# V1_5.net
KiCad netlist of a schematic drawn in Altium Designer
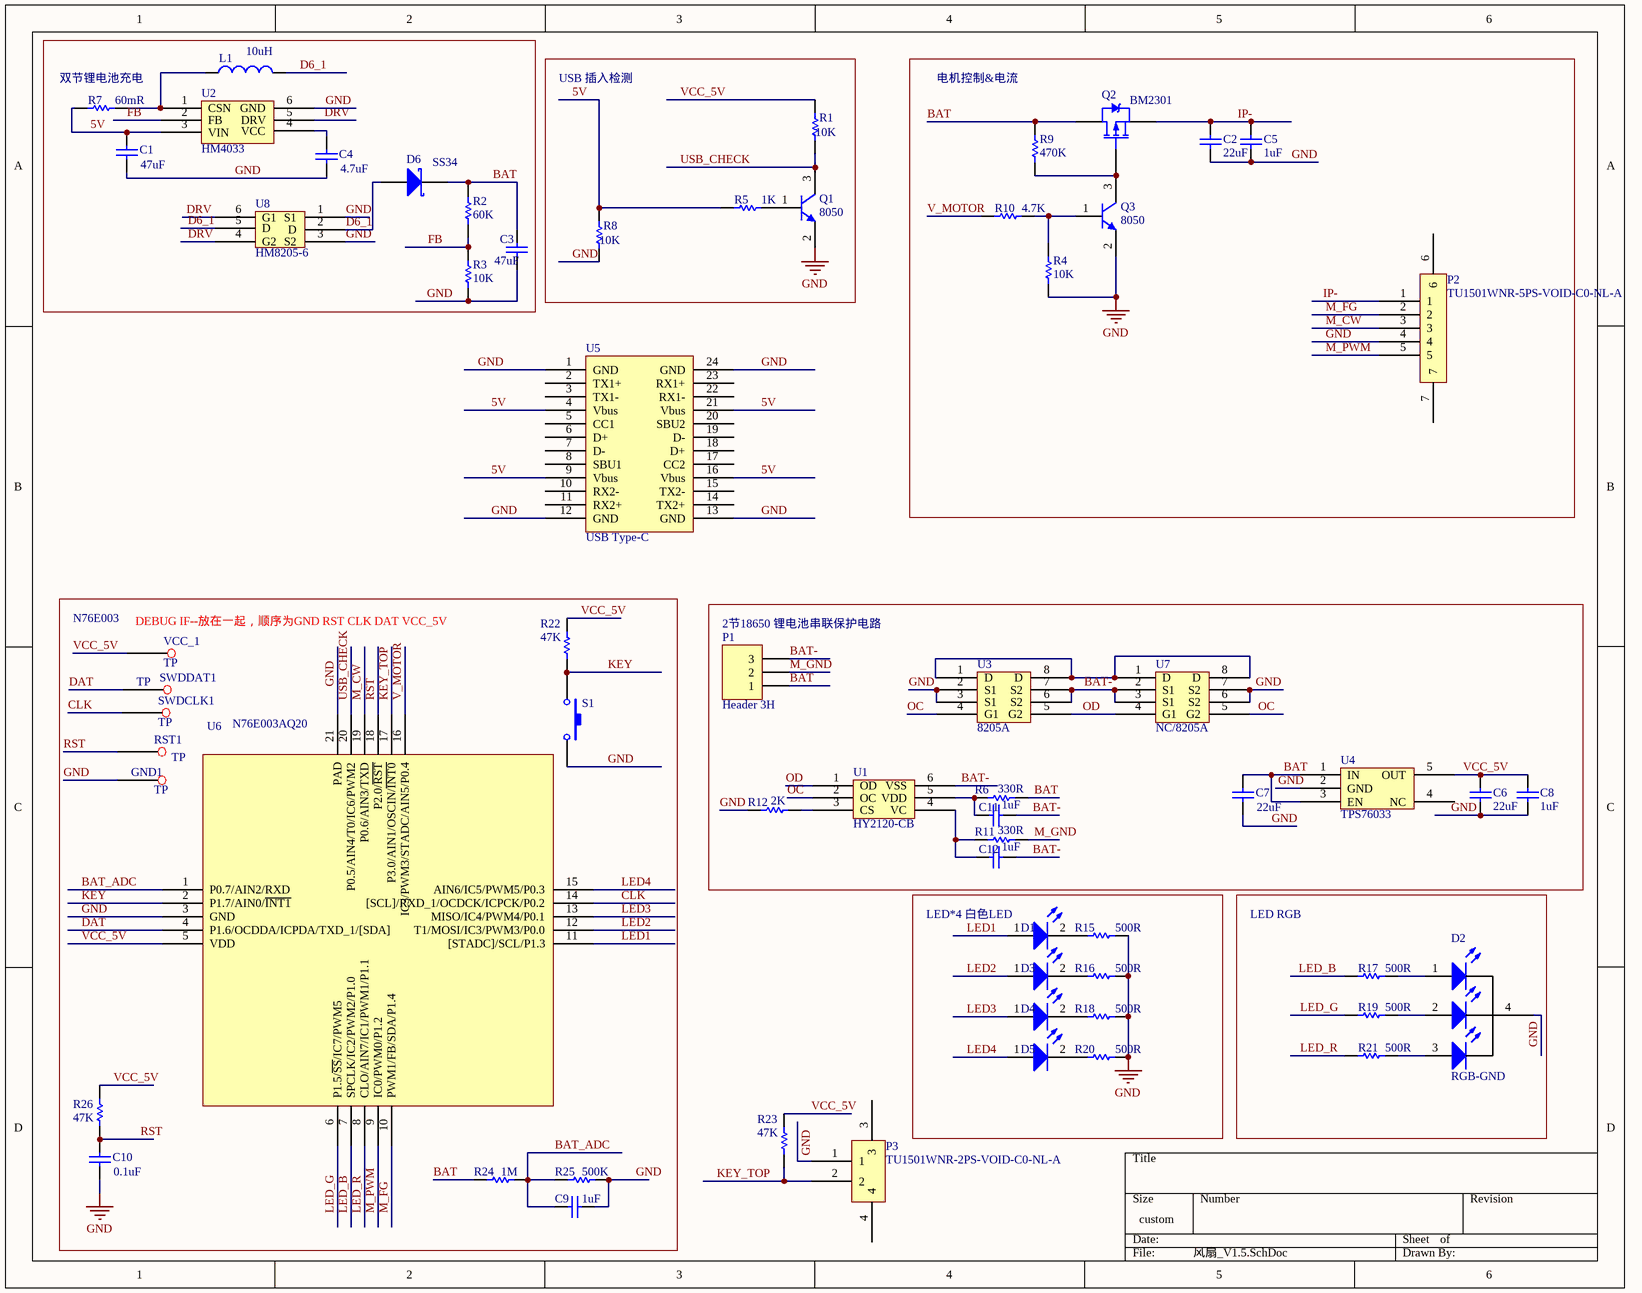
[diagram p0: 风扇_V1.5.SchDoc]

(export (version "E")
  (design (tool "Eeschema 10.0.6"))
  (components
    (comp (ref "C1")
      (value "47uF")
      (footprint "C-0603")
      (description "Capacitor")
      (fields (field (name "PUBLISHER") "Altium Limited"))
      (libsource (lib "Miscellaneous Devices") (part "Cap"))
    )
    (comp (ref "C2")
      (value "22uF")
      (footprint "C-0603")
      (description "Capacitor")
      (fields (field (name "PUBLISHER") "Altium Limited"))
      (libsource (lib "Miscellaneous Devices") (part "Cap"))
    )
    (comp (ref "C3")
      (value "47uF")
      (footprint "C-0603")
      (description "Capacitor")
      (fields (field (name "PUBLISHER") "Altium Limited"))
      (libsource (lib "Miscellaneous Devices") (part "Cap"))
    )
    (comp (ref "C4")
      (value "4.7uF")
      (footprint "C-0402")
      (description "Capacitor")
      (fields (field (name "PUBLISHER") "Altium Limited"))
      (libsource (lib "Miscellaneous Devices") (part "Cap"))
    )
    (comp (ref "C5")
      (value "1uF")
      (footprint "C-0402")
      (description "Capacitor")
      (fields (field (name "PUBLISHER") "Altium Limited"))
      (libsource (lib "Miscellaneous Devices") (part "Cap"))
    )
    (comp (ref "C6")
      (value "22uF")
      (footprint "C-0603")
      (description "Capacitor")
      (fields (field (name "PUBLISHER") "Altium Limited"))
      (libsource (lib "Miscellaneous Devices") (part "Cap"))
    )
    (comp (ref "C7")
      (value "22uF")
      (footprint "C-0603")
      (description "Capacitor")
      (fields (field (name "PUBLISHER") "Altium Limited"))
      (libsource (lib "Miscellaneous Devices") (part "Cap"))
    )
    (comp (ref "C8")
      (value "1uF")
      (footprint "C-0402")
      (description "Capacitor")
      (fields (field (name "PUBLISHER") "Altium Limited"))
      (libsource (lib "Miscellaneous Devices") (part "Cap"))
    )
    (comp (ref "C9")
      (value "1uF")
      (footprint "C-0402")
      (description "Capacitor")
      (fields (field (name "PUBLISHER") "Altium Limited"))
      (libsource (lib "Miscellaneous Devices") (part "Cap"))
    )
    (comp (ref "C10")
      (value "0.1uF")
      (footprint "C-0402")
      (description "Capacitor")
      (fields (field (name "PUBLISHER") "Altium Limited"))
      (libsource (lib "Miscellaneous Devices") (part "Cap"))
    )
    (comp (ref "C11")
      (value "1uF")
      (footprint "C-0402")
      (description "Capacitor")
      (fields (field (name "PUBLISHER") "Altium Limited"))
      (libsource (lib "Miscellaneous Devices") (part "Cap"))
    )
    (comp (ref "C12")
      (value "1uF")
      (footprint "C-0402")
      (description "Capacitor")
      (fields (field (name "PUBLISHER") "Altium Limited"))
      (libsource (lib "Miscellaneous Devices") (part "Cap"))
    )
    (comp (ref "D1")
      (value "LED0")
      (footprint "LED-0603")
      (description "Typical INFRARED GaAs LED")
      (fields (field (name "PUBLISHER") "Altium Limited"))
      (libsource (lib "Miscellaneous Devices") (part "LED0"))
    )
    (comp (ref "D2")
      (value "RGB-GND")
      (footprint "0603*2-LED")
      (libsource (lib "Others_IC_SCH_LIB") (part "RGB-GND"))
    )
    (comp (ref "D3")
      (value "LED0")
      (footprint "LED-0603")
      (description "Typical INFRARED GaAs LED")
      (fields (field (name "PUBLISHER") "Altium Limited"))
      (libsource (lib "Miscellaneous Devices") (part "LED0"))
    )
    (comp (ref "D4")
      (value "LED0")
      (footprint "LED-0603")
      (description "Typical INFRARED GaAs LED")
      (fields (field (name "PUBLISHER") "Altium Limited"))
      (libsource (lib "Miscellaneous Devices") (part "LED0"))
    )
    (comp (ref "D5")
      (value "LED0")
      (footprint "LED-0603")
      (description "Typical INFRARED GaAs LED")
      (fields (field (name "PUBLISHER") "Altium Limited"))
      (libsource (lib "Miscellaneous Devices") (part "LED0"))
    )
    (comp (ref "D6")
      (value "SS34")
      (footprint "HM4033 V1.0:DSMD")
      (description "Schottky Rectifier")
      (fields (field (name "PUBLISHER") "Altium Limited"))
      (libsource (lib "Miscellaneous Devices") (part "Diode 10TQ035"))
    )
    (comp (ref "GND1") (value "TP") (footprint "TP-1.5") (libsource (lib "Others_IC_SCH_LIB") (part "TP")))
    (comp (ref "L1")
      (value "10uH")
      (footprint "L-SMD")
      (description "Inductor")
      (fields (field (name "PUBLISHER") "Altium Limited"))
      (libsource (lib "Miscellaneous Devices") (part "Inductor"))
    )
    (comp (ref "P1")
      (value "Header 3H")
      (footprint "3P-SMT-3*3")
      (description "Header, 3-Pin, Right Angle")
      (fields (field (name "PUBLISHER") "Altium Limited"))
      (libsource (lib "Miscellaneous Connectors") (part "Header 3H"))
    )
    (comp (ref "P2")
      (value "TU1501WNR-5PS-VOID-C0-NL-A")
      (footprint "TU1501WNR-5PS-VOID-*-NL-A")
      (libsource (lib "Others_IC_SCH_LIB") (part "TU1501WNR-5PS-VOID-C0-NL-A"))
    )
    (comp (ref "P3")
      (value "TU1501WNR-2PS-VOID-C0-NL-A")
      (footprint "TU1501WNR-2PS-VOID-*-NL-A")
      (libsource (lib "Others_IC_SCH_LIB") (part "TU1501WNR-2PS-VOID-C0-NL-A"))
    )
    (comp (ref "Q1")
      (value "8050")
      (footprint "SOT-23")
      (description "NPN Bipolar Transistor")
      (fields (field (name "PUBLISHER") "Altium Limited"))
      (libsource (lib "Miscellaneous Devices") (part "NPN"))
    )
    (comp (ref "Q2")
      (value "BM2301")
      (footprint "SOT-23")
      (description "P-Channel Power MOSFET")
      (fields (field (name "PUBLISHER") "Altium Limited"))
      (libsource (lib "Miscellaneous Devices") (part "PMOS-2"))
    )
    (comp (ref "Q3")
      (value "8050")
      (footprint "SOT-23")
      (description "NPN Bipolar Transistor")
      (fields (field (name "PUBLISHER") "Altium Limited"))
      (libsource (lib "Miscellaneous Devices") (part "NPN"))
    )
    (comp (ref "R1")
      (value "10K")
      (footprint "R-0402")
      (description "Resistor")
      (fields (field (name "PUBLISHER") "Altium Limited"))
      (libsource (lib "Miscellaneous Devices") (part "Res1"))
    )
    (comp (ref "R2")
      (value "60K")
      (footprint "R-0402")
      (description "Resistor")
      (fields (field (name "PUBLISHER") "Altium Limited"))
      (libsource (lib "Miscellaneous Devices") (part "Res1"))
    )
    (comp (ref "R3")
      (value "10K")
      (footprint "R-0402")
      (description "Resistor")
      (fields (field (name "PUBLISHER") "Altium Limited"))
      (libsource (lib "Miscellaneous Devices") (part "Res1"))
    )
    (comp (ref "R4")
      (value "10K")
      (footprint "R-0402")
      (description "Resistor")
      (fields (field (name "PUBLISHER") "Altium Limited"))
      (libsource (lib "Miscellaneous Devices") (part "Res1"))
    )
    (comp (ref "R5")
      (value "1K")
      (footprint "R-0402")
      (description "Resistor")
      (fields (field (name "PUBLISHER") "Altium Limited"))
      (libsource (lib "Miscellaneous Devices") (part "Res1"))
    )
    (comp (ref "R6")
      (value "330R")
      (footprint "R-0402")
      (description "Resistor")
      (fields (field (name "PUBLISHER") "Altium Limited"))
      (libsource (lib "Miscellaneous Devices") (part "Res1"))
    )
    (comp (ref "R7")
      (value "60mR")
      (footprint "R-0402")
      (description "Resistor")
      (fields (field (name "PUBLISHER") "Altium Limited"))
      (libsource (lib "Miscellaneous Devices") (part "Res1"))
    )
    (comp (ref "R8")
      (value "10K")
      (footprint "R-0402")
      (description "Resistor")
      (fields (field (name "PUBLISHER") "Altium Limited"))
      (libsource (lib "Miscellaneous Devices") (part "Res1"))
    )
    (comp (ref "R9")
      (value "470K")
      (footprint "R-0402")
      (description "Resistor")
      (fields (field (name "PUBLISHER") "Altium Limited"))
      (libsource (lib "Miscellaneous Devices") (part "Res1"))
    )
    (comp (ref "R10")
      (value "4.7K")
      (footprint "R-0402")
      (description "Resistor")
      (fields (field (name "PUBLISHER") "Altium Limited"))
      (libsource (lib "Miscellaneous Devices") (part "Res1"))
    )
    (comp (ref "R11")
      (value "330R")
      (footprint "R-0402")
      (description "Resistor")
      (fields (field (name "PUBLISHER") "Altium Limited"))
      (libsource (lib "Miscellaneous Devices") (part "Res1"))
    )
    (comp (ref "R12")
      (value "2K")
      (footprint "R-0402")
      (description "Resistor")
      (fields (field (name "PUBLISHER") "Altium Limited"))
      (libsource (lib "Miscellaneous Devices") (part "Res1"))
    )
    (comp (ref "R15")
      (value "500R")
      (footprint "R-0402")
      (description "Resistor")
      (fields (field (name "PUBLISHER") "Altium Limited"))
      (libsource (lib "Miscellaneous Devices") (part "Res1"))
    )
    (comp (ref "R16")
      (value "500R")
      (footprint "R-0402")
      (description "Resistor")
      (fields (field (name "PUBLISHER") "Altium Limited"))
      (libsource (lib "Miscellaneous Devices") (part "Res1"))
    )
    (comp (ref "R17")
      (value "500R")
      (footprint "R-0402")
      (description "Resistor")
      (fields (field (name "PUBLISHER") "Altium Limited"))
      (libsource (lib "Miscellaneous Devices") (part "Res1"))
    )
    (comp (ref "R18")
      (value "500R")
      (footprint "R-0402")
      (description "Resistor")
      (fields (field (name "PUBLISHER") "Altium Limited"))
      (libsource (lib "Miscellaneous Devices") (part "Res1"))
    )
    (comp (ref "R19")
      (value "500R")
      (footprint "R-0402")
      (description "Resistor")
      (fields (field (name "PUBLISHER") "Altium Limited"))
      (libsource (lib "Miscellaneous Devices") (part "Res1"))
    )
    (comp (ref "R20")
      (value "500R")
      (footprint "R-0402")
      (description "Resistor")
      (fields (field (name "PUBLISHER") "Altium Limited"))
      (libsource (lib "Miscellaneous Devices") (part "Res1"))
    )
    (comp (ref "R21")
      (value "500R")
      (footprint "R-0402")
      (description "Resistor")
      (fields (field (name "PUBLISHER") "Altium Limited"))
      (libsource (lib "Miscellaneous Devices") (part "Res1"))
    )
    (comp (ref "R22")
      (value "47K")
      (footprint "R-0402")
      (description "Resistor")
      (fields (field (name "PUBLISHER") "Altium Limited"))
      (libsource (lib "Miscellaneous Devices") (part "Res1"))
    )
    (comp (ref "R23")
      (value "47K")
      (footprint "R-0402")
      (description "Resistor")
      (fields (field (name "PUBLISHER") "Altium Limited"))
      (libsource (lib "Miscellaneous Devices") (part "Res1"))
    )
    (comp (ref "R24")
      (value "1M")
      (footprint "R-0402")
      (description "Resistor")
      (fields (field (name "PUBLISHER") "Altium Limited"))
      (libsource (lib "Miscellaneous Devices") (part "Res1"))
    )
    (comp (ref "R25")
      (value "500K")
      (footprint "R-0402")
      (description "Resistor")
      (fields (field (name "PUBLISHER") "Altium Limited"))
      (libsource (lib "Miscellaneous Devices") (part "Res1"))
    )
    (comp (ref "R26")
      (value "47K")
      (footprint "R-0402")
      (description "Resistor")
      (fields (field (name "PUBLISHER") "Altium Limited"))
      (libsource (lib "Miscellaneous Devices") (part "Res1"))
    )
    (comp (ref "RST1") (value "TP") (footprint "TP-1.5") (libsource (lib "Others_IC_SCH_LIB") (part "TP")))
    (comp (ref "S1")
      (value "SW-PB")
      (footprint "SWITCH-4P-SMT")
      (description "Switch")
      (fields (field (name "PUBLISHER") "Altium Limited"))
      (libsource (lib "Miscellaneous Devices") (part "SW-PB"))
    )
    (comp (ref "SWDCLK1") (value "TP") (footprint "TP-1.5") (libsource (lib "Others_IC_SCH_LIB") (part "TP")))
    (comp (ref "SWDDAT1") (value "TP") (footprint "TP-1.5") (libsource (lib "Others_IC_SCH_LIB") (part "TP")))
    (comp (ref "U1")
      (value "HY2120-CB")
      (footprint "SOT-23-6L")
      (libsource (lib "Others_IC_SCH_LIB") (part "HY2120"))
    )
    (comp (ref "U2")
      (value "HM4033")
      (footprint "SOT-23-6L")
      (libsource (lib "Others_IC_SCH_LIB") (part "HM4033"))
    )
    (comp (ref "U3")
      (value "8205A")
      (footprint "TSSOP8")
      (libsource (lib "Others_IC_SCH_LIB") (part "8205A"))
    )
    (comp (ref "U4")
      (value "TPS76033")
      (footprint "SOT-23-5")
      (libsource (lib "Others_IC_SCH_LIB") (part "TPS76033"))
    )
    (comp (ref "U5")
      (value "USB Type-C")
      (footprint "USB-type C")
      (libsource (lib "Others_IC_SCH_LIB") (part "USB Type-C"))
    )
    (comp (ref "U6")
      (value "N76E003AQ20")
      (footprint "QFN-20 0.4mm")
      (libsource (lib "Others_IC_SCH_LIB") (part "N76E003AQ20"))
    )
    (comp (ref "U7")
      (value "NC/8205A")
      (footprint "TSSOP8")
      (libsource (lib "Others_IC_SCH_LIB") (part "8205A"))
    )
    (comp (ref "U8")
      (value "HM8205-6")
      (footprint "SOT-23-6L")
      (libsource (lib "Others_IC_SCH_LIB") (part "HM8205-6"))
    )
    (comp (ref "VCC_1") (value "TP") (footprint "TP-1.5") (libsource (lib "Others_IC_SCH_LIB") (part "TP")))
  )
  (nets
    (net (code "1") (name "/5V") (class "Default")
      (node (ref "C1") (pin "1") (pinfunction "1_1") (pintype "passive"))
      (node (ref "R5") (pin "1") (pinfunction "1_1") (pintype "passive"))
      (node (ref "R7") (pin "2") (pinfunction "2_2") (pintype "passive"))
      (node (ref "R8") (pin "1") (pinfunction "1_1") (pintype "passive"))
      (node (ref "U2") (pin "3") (pinfunction "VIN_3") (pintype "passive"))
      (node (ref "U5") (pin "16") (pinfunction "Vbus_16") (pintype "passive"))
      (node (ref "U5") (pin "21") (pinfunction "Vbus_21") (pintype "passive"))
      (node (ref "U5") (pin "4") (pinfunction "Vbus_4") (pintype "passive"))
      (node (ref "U5") (pin "9") (pinfunction "Vbus_9") (pintype "passive"))
    )
    (net (code "2") (name "/BAT") (class "Default")
      (node (ref "C3") (pin "2") (pinfunction "2_2") (pintype "passive"))
      (node (ref "C7") (pin "2") (pinfunction "2_2") (pintype "passive"))
      (node (ref "D6") (pin "1") (pinfunction "K_1") (pintype "passive"))
      (node (ref "P1") (pin "1") (pinfunction "1_1") (pintype "passive"))
      (node (ref "Q2") (pin "2") (pinfunction "D_2") (pintype "passive"))
      (node (ref "R2") (pin "1") (pinfunction "1_1") (pintype "passive"))
      (node (ref "R24") (pin "1") (pinfunction "1_1") (pintype "passive"))
      (node (ref "R6") (pin "2") (pinfunction "2_2") (pintype "passive"))
      (node (ref "R9") (pin "2") (pinfunction "2_2") (pintype "passive"))
      (node (ref "U4") (pin "1") (pinfunction "IN_1") (pintype "passive"))
      (node (ref "U4") (pin "3") (pinfunction "EN_3") (pintype "passive"))
    )
    (net (code "3") (name "/BAT-") (class "Default")
      (node (ref "C11") (pin "1") (pinfunction "1_1") (pintype "passive"))
      (node (ref "C12") (pin "1") (pinfunction "1_1") (pintype "passive"))
      (node (ref "P1") (pin "3") (pinfunction "3_3") (pintype "passive"))
      (node (ref "U1") (pin "6") (pinfunction "VSS_6") (pintype "passive"))
      (node (ref "U3") (pin "6") (pinfunction "S2_6") (pintype "passive"))
      (node (ref "U3") (pin "7") (pinfunction "S2_7") (pintype "passive"))
      (node (ref "U7") (pin "2") (pinfunction "S1_2") (pintype "passive"))
      (node (ref "U7") (pin "3") (pinfunction "S1_3") (pintype "passive"))
    )
    (net (code "4") (name "/BAT_ADC") (class "Default")
      (node (ref "C9") (pin "2") (pinfunction "2_2") (pintype "passive"))
      (node (ref "R24") (pin "2") (pinfunction "2_2") (pintype "passive"))
      (node (ref "R25") (pin "1") (pinfunction "1_1") (pintype "passive"))
      (node (ref "U6") (pin "1") (pinfunction "P0.7/AIN2/RXD_1") (pintype "passive"))
    )
    (net (code "5") (name "/CLK") (class "Default")
      (node (ref "SWDCLK1") (pin "1") (pinfunction "1_1") (pintype "passive"))
      (node (ref "U6") (pin "14") (pinfunction "[SCL]/RXD_1/OCDCK/ICPCK/P0.2_14") (pintype "passive"))
    )
    (net (code "6") (name "/D6_1") (class "Default")
      (node (ref "D6") (pin "3") (pinfunction "A_3") (pintype "passive"))
      (node (ref "L1") (pin "2") (pinfunction "2_2") (pintype "passive"))
      (node (ref "U8") (pin "2") (pinfunction "D_2") (pintype "passive"))
      (node (ref "U8") (pin "5") (pinfunction "D_5") (pintype "passive"))
    )
    (net (code "7") (name "/DAT") (class "Default")
      (node (ref "SWDDAT1") (pin "1") (pinfunction "1_1") (pintype "passive"))
      (node (ref "U6") (pin "4") (pinfunction "P1.6/OCDDA/ICPDA/TXD_1/[SDA]_4") (pintype "passive"))
    )
    (net (code "8") (name "/DRV") (class "Default")
      (node (ref "U2") (pin "5") (pinfunction "DRV_5") (pintype "passive"))
      (node (ref "U8") (pin "4") (pinfunction "G2_4") (pintype "passive"))
      (node (ref "U8") (pin "6") (pinfunction "G1_6") (pintype "passive"))
    )
    (net (code "9") (name "/FB") (class "Default")
      (node (ref "R2") (pin "2") (pinfunction "2_2") (pintype "passive"))
      (node (ref "R3") (pin "1") (pinfunction "1_1") (pintype "passive"))
      (node (ref "U2") (pin "2") (pinfunction "FB_2") (pintype "passive"))
    )
    (net (code "10") (name "/IP-") (class "Default")
      (node (ref "C2") (pin "2") (pinfunction "2_2") (pintype "passive"))
      (node (ref "C5") (pin "2") (pinfunction "2_2") (pintype "passive"))
      (node (ref "P2") (pin "1") (pinfunction "1_1") (pintype "passive"))
      (node (ref "Q2") (pin "3") (pinfunction "S_3") (pintype "passive"))
    )
    (net (code "11") (name "/KEY") (class "Default")
      (node (ref "R22") (pin "1") (pinfunction "1_1") (pintype "passive"))
      (node (ref "S1") (pin "1") (pinfunction "1_1") (pintype "passive"))
      (node (ref "U6") (pin "2") (pinfunction "P1.7/AIN0/~{INT1}_2") (pintype "passive"))
    )
    (net (code "12") (name "/KEY_TOP") (class "Default")
      (node (ref "P3") (pin "2") (pinfunction "2_2") (pintype "passive"))
      (node (ref "R23") (pin "1") (pinfunction "1_1") (pintype "passive"))
      (node (ref "U6") (pin "17") (pinfunction "P3.0/AIN1/OSCIN/~{INT0}_17") (pintype "passive"))
    )
    (net (code "13") (name "/LED1") (class "Default")
      (node (ref "D1") (pin "1") (pinfunction "A_1") (pintype "passive"))
      (node (ref "U6") (pin "11") (pinfunction "[STADC]/SCL/P1.3_11") (pintype "passive"))
    )
    (net (code "14") (name "/LED2") (class "Default")
      (node (ref "D3") (pin "1") (pinfunction "A_1") (pintype "passive"))
      (node (ref "U6") (pin "12") (pinfunction "T1/MOSI/IC3/PWM3/P0.0_12") (pintype "passive"))
    )
    (net (code "15") (name "/LED3") (class "Default")
      (node (ref "D4") (pin "1") (pinfunction "A_1") (pintype "passive"))
      (node (ref "U6") (pin "13") (pinfunction "MISO/IC4/PWM4/P0.1_13") (pintype "passive"))
    )
    (net (code "16") (name "/LED4") (class "Default")
      (node (ref "D5") (pin "1") (pinfunction "A_1") (pintype "passive"))
      (node (ref "U6") (pin "15") (pinfunction "AIN6/IC5/PWM5/P0.3_15") (pintype "passive"))
    )
    (net (code "17") (name "/LED_B") (class "Default")
      (node (ref "R17") (pin "1") (pinfunction "1_1") (pintype "passive"))
      (node (ref "U6") (pin "7") (pinfunction "SPCLK/IC2/PWM2/P1.0_7") (pintype "passive"))
    )
    (net (code "18") (name "/LED_G") (class "Default")
      (node (ref "R19") (pin "1") (pinfunction "1_1") (pintype "passive"))
      (node (ref "U6") (pin "6") (pinfunction "P1.5/~{SS}/IC7/PWM5_6") (pintype "passive"))
    )
    (net (code "19") (name "/LED_R") (class "Default")
      (node (ref "R21") (pin "1") (pinfunction "1_1") (pintype "passive"))
      (node (ref "U6") (pin "8") (pinfunction "CLO/AIN7/IC1/PWM1/P1.1_8") (pintype "passive"))
    )
    (net (code "20") (name "/M_CW") (class "Default")
      (node (ref "P2") (pin "3") (pinfunction "3_3") (pintype "passive"))
      (node (ref "U6") (pin "19") (pinfunction "P0.6/AIN3/TXD_19") (pintype "passive"))
    )
    (net (code "21") (name "/M_FG") (class "Default")
      (node (ref "P2") (pin "2") (pinfunction "2_2") (pintype "passive"))
      (node (ref "U6") (pin "10") (pinfunction "PWM1/FB/SDA/P1.4_10") (pintype "passive"))
    )
    (net (code "22") (name "/M_GND") (class "Default")
      (node (ref "P1") (pin "2") (pinfunction "2_2") (pintype "passive"))
      (node (ref "R11") (pin "2") (pinfunction "2_2") (pintype "passive"))
    )
    (net (code "23") (name "/M_PWM") (class "Default")
      (node (ref "P2") (pin "5") (pinfunction "5_5") (pintype "passive"))
      (node (ref "U6") (pin "9") (pinfunction "IC0/PWM0/P1.2_9") (pintype "passive"))
    )
    (net (code "24") (name "/OC") (class "Default")
      (node (ref "U1") (pin "2") (pinfunction "OC_2") (pintype "passive"))
      (node (ref "U3") (pin "4") (pinfunction "G1_4") (pintype "passive"))
      (node (ref "U7") (pin "5") (pinfunction "G2_5") (pintype "passive"))
    )
    (net (code "25") (name "/OD") (class "Default")
      (node (ref "U1") (pin "1") (pinfunction "OD_1") (pintype "passive"))
      (node (ref "U3") (pin "5") (pinfunction "G2_5") (pintype "passive"))
      (node (ref "U7") (pin "4") (pinfunction "G1_4") (pintype "passive"))
    )
    (net (code "26") (name "/RST") (class "Default")
      (node (ref "C10") (pin "2") (pinfunction "2_2") (pintype "passive"))
      (node (ref "R26") (pin "1") (pinfunction "1_1") (pintype "passive"))
      (node (ref "RST1") (pin "1") (pinfunction "1_1") (pintype "passive"))
      (node (ref "U6") (pin "18") (pinfunction "P2.0/~{RST}_18") (pintype "passive"))
    )
    (net (code "27") (name "/USB_CHECK") (class "Default")
      (node (ref "Q1") (pin "3") (pinfunction "C_3") (pintype "passive"))
      (node (ref "R1") (pin "1") (pinfunction "1_1") (pintype "passive"))
      (node (ref "U6") (pin "20") (pinfunction "P0.5/AIN4/T0/IC6/PWM2_20") (pintype "passive"))
    )
    (net (code "28") (name "/VCC_5V") (class "Default")
      (node (ref "C6") (pin "2") (pinfunction "2_2") (pintype "passive"))
      (node (ref "C8") (pin "2") (pinfunction "2_2") (pintype "passive"))
      (node (ref "R1") (pin "2") (pinfunction "2_2") (pintype "passive"))
      (node (ref "R22") (pin "2") (pinfunction "2_2") (pintype "passive"))
      (node (ref "R23") (pin "2") (pinfunction "2_2") (pintype "passive"))
      (node (ref "R26") (pin "2") (pinfunction "2_2") (pintype "passive"))
      (node (ref "U4") (pin "5") (pinfunction "OUT_5") (pintype "passive"))
      (node (ref "U6") (pin "5") (pinfunction "VDD_5") (pintype "passive"))
      (node (ref "VCC_1") (pin "1") (pinfunction "1_1") (pintype "passive"))
    )
    (net (code "29") (name "/V_MOTOR") (class "Default")
      (node (ref "R10") (pin "1") (pinfunction "1_1") (pintype "passive"))
      (node (ref "U6") (pin "16") (pinfunction "IC3/PWM3/STADC/AIN5/P0.4_16") (pintype "passive"))
    )
    (net (code "30") (name "GND") (class "Default")
      (node (ref "C1") (pin "2") (pinfunction "2_2") (pintype "passive"))
      (node (ref "C10") (pin "1") (pinfunction "1_1") (pintype "passive"))
      (node (ref "C2") (pin "1") (pinfunction "1_1") (pintype "passive"))
      (node (ref "C3") (pin "1") (pinfunction "1_1") (pintype "passive"))
      (node (ref "C4") (pin "2") (pinfunction "2_2") (pintype "passive"))
      (node (ref "C5") (pin "1") (pinfunction "1_1") (pintype "passive"))
      (node (ref "C6") (pin "1") (pinfunction "1_1") (pintype "passive"))
      (node (ref "C7") (pin "1") (pinfunction "1_1") (pintype "passive"))
      (node (ref "C8") (pin "1") (pinfunction "1_1") (pintype "passive"))
      (node (ref "C9") (pin "1") (pinfunction "1_1") (pintype "passive"))
      (node (ref "D2") (pin "4") (pinfunction "4_4") (pintype "passive"))
      (node (ref "GND1") (pin "1") (pinfunction "1_1") (pintype "passive"))
      (node (ref "P2") (pin "4") (pinfunction "4_4") (pintype "passive"))
      (node (ref "P3") (pin "1") (pinfunction "1_1") (pintype "passive"))
      (node (ref "Q1") (pin "2") (pinfunction "E_2") (pintype "passive"))
      (node (ref "Q3") (pin "2") (pinfunction "E_2") (pintype "passive"))
      (node (ref "R12") (pin "1") (pinfunction "1_1") (pintype "passive"))
      (node (ref "R15") (pin "2") (pinfunction "2_2") (pintype "passive"))
      (node (ref "R16") (pin "2") (pinfunction "2_2") (pintype "passive"))
      (node (ref "R18") (pin "2") (pinfunction "2_2") (pintype "passive"))
      (node (ref "R20") (pin "2") (pinfunction "2_2") (pintype "passive"))
      (node (ref "R25") (pin "2") (pinfunction "2_2") (pintype "passive"))
      (node (ref "R3") (pin "2") (pinfunction "2_2") (pintype "passive"))
      (node (ref "R4") (pin "1") (pinfunction "1_1") (pintype "passive"))
      (node (ref "R8") (pin "2") (pinfunction "2_2") (pintype "passive"))
      (node (ref "S1") (pin "2") (pinfunction "2_2") (pintype "passive"))
      (node (ref "U2") (pin "6") (pinfunction "GND_6") (pintype "passive"))
      (node (ref "U3") (pin "2") (pinfunction "S1_2") (pintype "passive"))
      (node (ref "U3") (pin "3") (pinfunction "S1_3") (pintype "passive"))
      (node (ref "U4") (pin "2") (pinfunction "GND_2") (pintype "passive"))
      (node (ref "U5") (pin "1") (pinfunction "GND_1") (pintype "passive"))
      (node (ref "U5") (pin "12") (pinfunction "GND_12") (pintype "passive"))
      (node (ref "U5") (pin "13") (pinfunction "GND_13") (pintype "passive"))
      (node (ref "U5") (pin "24") (pinfunction "GND_24") (pintype "passive"))
      (node (ref "U6") (pin "21") (pinfunction "PAD_21") (pintype "passive"))
      (node (ref "U6") (pin "3") (pinfunction "GND_3") (pintype "passive"))
      (node (ref "U7") (pin "6") (pinfunction "S2_6") (pintype "passive"))
      (node (ref "U7") (pin "7") (pinfunction "S2_7") (pintype "passive"))
      (node (ref "U8") (pin "1") (pinfunction "S1_1") (pintype "passive"))
      (node (ref "U8") (pin "3") (pinfunction "S2_3") (pintype "passive"))
    )
    (net (code "31") (name "Net-(D1-K)") (class "Default")
      (node (ref "D1") (pin "2") (pinfunction "K_2") (pintype "passive"))
      (node (ref "R15") (pin "1") (pinfunction "1_1") (pintype "passive"))
    )
    (net (code "32") (name "Net-(D2-Pad1)") (class "Default")
      (node (ref "D2") (pin "1") (pinfunction "1_1") (pintype "passive"))
      (node (ref "R17") (pin "2") (pinfunction "2_2") (pintype "passive"))
    )
    (net (code "33") (name "Net-(D2-Pad2)") (class "Default")
      (node (ref "D2") (pin "2") (pinfunction "2_2") (pintype "passive"))
      (node (ref "R19") (pin "2") (pinfunction "2_2") (pintype "passive"))
    )
    (net (code "34") (name "Net-(D2-Pad3)") (class "Default")
      (node (ref "D2") (pin "3") (pinfunction "3_3") (pintype "passive"))
      (node (ref "R21") (pin "2") (pinfunction "2_2") (pintype "passive"))
    )
    (net (code "35") (name "Net-(D3-K)") (class "Default")
      (node (ref "D3") (pin "2") (pinfunction "K_2") (pintype "passive"))
      (node (ref "R16") (pin "1") (pinfunction "1_1") (pintype "passive"))
    )
    (net (code "36") (name "Net-(D4-K)") (class "Default")
      (node (ref "D4") (pin "2") (pinfunction "K_2") (pintype "passive"))
      (node (ref "R18") (pin "1") (pinfunction "1_1") (pintype "passive"))
    )
    (net (code "37") (name "Net-(D5-K)") (class "Default")
      (node (ref "D5") (pin "2") (pinfunction "K_2") (pintype "passive"))
      (node (ref "R20") (pin "1") (pinfunction "1_1") (pintype "passive"))
    )
    (net (code "38") (name "Net-(Q1-B)") (class "Default")
      (node (ref "Q1") (pin "1") (pinfunction "B_1") (pintype "passive"))
      (node (ref "R5") (pin "2") (pinfunction "2_2") (pintype "passive"))
    )
    (net (code "39") (name "Net-(Q2-G)") (class "Default")
      (node (ref "Q2") (pin "1") (pinfunction "G_1") (pintype "passive"))
      (node (ref "Q3") (pin "3") (pinfunction "C_3") (pintype "passive"))
      (node (ref "R9") (pin "1") (pinfunction "1_1") (pintype "passive"))
    )
    (net (code "40") (name "Net-(Q3-B)") (class "Default")
      (node (ref "Q3") (pin "1") (pinfunction "B_1") (pintype "passive"))
      (node (ref "R10") (pin "2") (pinfunction "2_2") (pintype "passive"))
      (node (ref "R4") (pin "2") (pinfunction "2_2") (pintype "passive"))
    )
    (net (code "41") (name "Net-(U1-CS)") (class "Default")
      (node (ref "R12") (pin "2") (pinfunction "2_2") (pintype "passive"))
      (node (ref "U1") (pin "3") (pinfunction "CS_3") (pintype "passive"))
    )
    (net (code "42") (name "Net-(U1-VC)") (class "Default")
      (node (ref "C12") (pin "2") (pinfunction "2_2") (pintype "passive"))
      (node (ref "R11") (pin "1") (pinfunction "1_1") (pintype "passive"))
      (node (ref "U1") (pin "4") (pinfunction "VC_4") (pintype "passive"))
    )
    (net (code "43") (name "Net-(U1-VDD)") (class "Default")
      (node (ref "C11") (pin "2") (pinfunction "2_2") (pintype "passive"))
      (node (ref "R6") (pin "1") (pinfunction "1_1") (pintype "passive"))
      (node (ref "U1") (pin "5") (pinfunction "VDD_5") (pintype "passive"))
    )
    (net (code "44") (name "Net-(U2-CSN)") (class "Default")
      (node (ref "L1") (pin "1") (pinfunction "1_1") (pintype "passive"))
      (node (ref "R7") (pin "1") (pinfunction "1_1") (pintype "passive"))
      (node (ref "U2") (pin "1") (pinfunction "CSN_1") (pintype "passive"))
    )
    (net (code "45") (name "Net-(U2-VCC)") (class "Default")
      (node (ref "C4") (pin "1") (pinfunction "1_1") (pintype "passive"))
      (node (ref "U2") (pin "4") (pinfunction "VCC_4") (pintype "passive"))
    )
    (net (code "46") (name "Net-(U3-D-Pad1)") (class "Default")
      (node (ref "U3") (pin "1") (pinfunction "D_1") (pintype "passive"))
      (node (ref "U3") (pin "8") (pinfunction "D_8") (pintype "passive"))
      (node (ref "U7") (pin "1") (pinfunction "D_1") (pintype "passive"))
      (node (ref "U7") (pin "8") (pinfunction "D_8") (pintype "passive"))
    )
    (net (code "47") (name "unconnected-(P2-Pad6)") (class "Default")
      (node (ref "P2") (pin "6") (pinfunction "6_6") (pintype "passive"))
    )
    (net (code "48") (name "unconnected-(P2-Pad7)") (class "Default")
      (node (ref "P2") (pin "7") (pinfunction "7_7") (pintype "passive"))
    )
    (net (code "49") (name "unconnected-(P3-Pad3)") (class "Default")
      (node (ref "P3") (pin "3") (pinfunction "3_3") (pintype "passive"))
    )
    (net (code "50") (name "unconnected-(P3-Pad4)") (class "Default")
      (node (ref "P3") (pin "4") (pinfunction "4_4") (pintype "passive"))
    )
    (net (code "51") (name "unconnected-(U4-NC-Pad4)") (class "Default")
      (node (ref "U4") (pin "4") (pinfunction "NC_4") (pintype "passive"))
    )
    (net (code "52") (name "unconnected-(U5-CC1-Pad5)") (class "Default")
      (node (ref "U5") (pin "5") (pinfunction "CC1_5") (pintype "passive"))
    )
    (net (code "53") (name "unconnected-(U5-CC2-Pad17)") (class "Default")
      (node (ref "U5") (pin "17") (pinfunction "CC2_17") (pintype "passive"))
    )
    (net (code "54") (name "unconnected-(U5-D+-Pad6)") (class "Default")
      (node (ref "U5") (pin "6") (pinfunction "D+_6") (pintype "passive"))
    )
    (net (code "55") (name "unconnected-(U5-D+-Pad18)") (class "Default")
      (node (ref "U5") (pin "18") (pinfunction "D+_18") (pintype "passive"))
    )
    (net (code "56") (name "unconnected-(U5-D--Pad7)") (class "Default")
      (node (ref "U5") (pin "7") (pinfunction "D-_7") (pintype "passive"))
    )
    (net (code "57") (name "unconnected-(U5-D--Pad19)") (class "Default")
      (node (ref "U5") (pin "19") (pinfunction "D-_19") (pintype "passive"))
    )
    (net (code "58") (name "unconnected-(U5-RX1+-Pad23)") (class "Default")
      (node (ref "U5") (pin "23") (pinfunction "RX1+_23") (pintype "passive"))
    )
    (net (code "59") (name "unconnected-(U5-RX1--Pad22)") (class "Default")
      (node (ref "U5") (pin "22") (pinfunction "RX1-_22") (pintype "passive"))
    )
    (net (code "60") (name "unconnected-(U5-RX2+-Pad11)") (class "Default")
      (node (ref "U5") (pin "11") (pinfunction "RX2+_11") (pintype "passive"))
    )
    (net (code "61") (name "unconnected-(U5-RX2--Pad10)") (class "Default")
      (node (ref "U5") (pin "10") (pinfunction "RX2-_10") (pintype "passive"))
    )
    (net (code "62") (name "unconnected-(U5-SBU1-Pad8)") (class "Default")
      (node (ref "U5") (pin "8") (pinfunction "SBU1_8") (pintype "passive"))
    )
    (net (code "63") (name "unconnected-(U5-SBU2-Pad20)") (class "Default")
      (node (ref "U5") (pin "20") (pinfunction "SBU2_20") (pintype "passive"))
    )
    (net (code "64") (name "unconnected-(U5-TX1+-Pad2)") (class "Default")
      (node (ref "U5") (pin "2") (pinfunction "TX1+_2") (pintype "passive"))
    )
    (net (code "65") (name "unconnected-(U5-TX1--Pad3)") (class "Default")
      (node (ref "U5") (pin "3") (pinfunction "TX1-_3") (pintype "passive"))
    )
    (net (code "66") (name "unconnected-(U5-TX2+-Pad14)") (class "Default")
      (node (ref "U5") (pin "14") (pinfunction "TX2+_14") (pintype "passive"))
    )
    (net (code "67") (name "unconnected-(U5-TX2--Pad15)") (class "Default")
      (node (ref "U5") (pin "15") (pinfunction "TX2-_15") (pintype "passive"))
    )
  )
)
